# Connector.net
KiCad netlist of a schematic drawn in Altium Designer
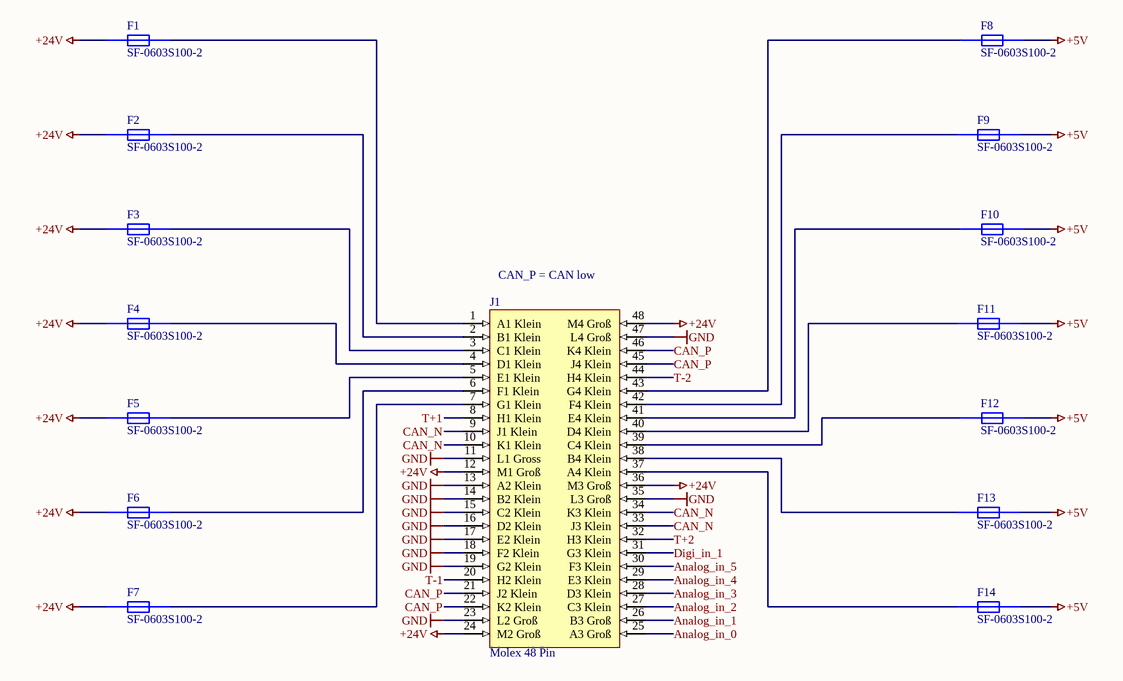
[diagram p0: Connector.SchDoc]

(export (version "E")
  (design (tool "Eeschema 10.0.6"))
  (components
    (comp (ref "F1")
      (value "SF-0603S100-2")
      (footprint "RESC1608X06N")
      (description "0603 SMD Slow Blow Fuse")
      (libsource (lib "LibMoritz") (part "SF-0603S100-2"))
    )
    (comp (ref "F2")
      (value "SF-0603S100-2")
      (footprint "RESC1608X06N")
      (description "0603 SMD Slow Blow Fuse")
      (libsource (lib "LibMoritz") (part "SF-0603S100-2"))
    )
    (comp (ref "F3")
      (value "SF-0603S100-2")
      (footprint "RESC1608X06N")
      (description "0603 SMD Slow Blow Fuse")
      (libsource (lib "LibMoritz") (part "SF-0603S100-2"))
    )
    (comp (ref "F4")
      (value "SF-0603S100-2")
      (footprint "RESC1608X06N")
      (description "0603 SMD Slow Blow Fuse")
      (libsource (lib "LibMoritz") (part "SF-0603S100-2"))
    )
    (comp (ref "F5")
      (value "SF-0603S100-2")
      (footprint "RESC1608X06N")
      (description "0603 SMD Slow Blow Fuse")
      (libsource (lib "LibMoritz") (part "SF-0603S100-2"))
    )
    (comp (ref "F6")
      (value "SF-0603S100-2")
      (footprint "RESC1608X06N")
      (description "0603 SMD Slow Blow Fuse")
      (libsource (lib "LibMoritz") (part "SF-0603S100-2"))
    )
    (comp (ref "F7")
      (value "SF-0603S100-2")
      (footprint "RESC1608X06N")
      (description "0603 SMD Slow Blow Fuse")
      (libsource (lib "LibMoritz") (part "SF-0603S100-2"))
    )
    (comp (ref "F8")
      (value "SF-0603S100-2")
      (footprint "RESC1608X06N")
      (description "0603 SMD Slow Blow Fuse")
      (libsource (lib "LibMoritz") (part "SF-0603S100-2"))
    )
    (comp (ref "F9")
      (value "SF-0603S100-2")
      (footprint "RESC1608X06N")
      (description "0603 SMD Slow Blow Fuse")
      (libsource (lib "LibMoritz") (part "SF-0603S100-2"))
    )
    (comp (ref "F10")
      (value "SF-0603S100-2")
      (footprint "RESC1608X06N")
      (description "0603 SMD Slow Blow Fuse")
      (libsource (lib "LibMoritz") (part "SF-0603S100-2"))
    )
    (comp (ref "F11")
      (value "SF-0603S100-2")
      (footprint "RESC1608X06N")
      (description "0603 SMD Slow Blow Fuse")
      (libsource (lib "LibMoritz") (part "SF-0603S100-2"))
    )
    (comp (ref "F12")
      (value "SF-0603S100-2")
      (footprint "RESC1608X06N")
      (description "0603 SMD Slow Blow Fuse")
      (libsource (lib "LibMoritz") (part "SF-0603S100-2"))
    )
    (comp (ref "F13")
      (value "SF-0603S100-2")
      (footprint "RESC1608X06N")
      (description "0603 SMD Slow Blow Fuse")
      (libsource (lib "LibMoritz") (part "SF-0603S100-2"))
    )
    (comp (ref "F14")
      (value "SF-0603S100-2")
      (footprint "RESC1608X06N")
      (description "0603 SMD Slow Blow Fuse")
      (libsource (lib "LibMoritz") (part "SF-0603S100-2"))
    )
    (comp (ref "J1")
      (value "Molex 48 Pin")
      (footprint "5007621001")
      (description "Molex 48 Pin CMC Header")
      (libsource (lib "LibMoritz") (part "5007621001"))
    )
  )
  (nets
    (net (code "1") (name "+5V") (class "Default")
      (node (ref "F10") (pin "2") (pinfunction "A2_2") (pintype "passive"))
      (node (ref "F11") (pin "2") (pinfunction "A2_2") (pintype "passive"))
      (node (ref "F12") (pin "2") (pinfunction "A2_2") (pintype "passive"))
      (node (ref "F13") (pin "2") (pinfunction "A2_2") (pintype "passive"))
      (node (ref "F14") (pin "2") (pinfunction "A2_2") (pintype "passive"))
      (node (ref "F8") (pin "2") (pinfunction "A2_2") (pintype "passive"))
      (node (ref "F9") (pin "2") (pinfunction "A2_2") (pintype "passive"))
    )
    (net (code "2") (name "+24V") (class "Default")
      (node (ref "F1") (pin "1") (pinfunction "A1_1") (pintype "passive"))
      (node (ref "F2") (pin "1") (pinfunction "A1_1") (pintype "passive"))
      (node (ref "F3") (pin "1") (pinfunction "A1_1") (pintype "passive"))
      (node (ref "F4") (pin "1") (pinfunction "A1_1") (pintype "passive"))
      (node (ref "F5") (pin "1") (pinfunction "A1_1") (pintype "passive"))
      (node (ref "F6") (pin "1") (pinfunction "A1_1") (pintype "passive"))
      (node (ref "F7") (pin "1") (pinfunction "A1_1") (pintype "passive"))
      (node (ref "J1") (pin "12") (pinfunction "M1_Groß_12") (pintype "input"))
      (node (ref "J1") (pin "24") (pinfunction "M2_Groß_24") (pintype "input"))
      (node (ref "J1") (pin "36") (pinfunction "M3_Groß_36") (pintype "input"))
      (node (ref "J1") (pin "48") (pinfunction "M4_Groß_48") (pintype "input"))
    )
    (net (code "3") (name "/Analog_in_0") (class "Default")
      (node (ref "J1") (pin "25") (pinfunction "A3_Groß_25") (pintype "input"))
    )
    (net (code "4") (name "/Analog_in_1") (class "Default")
      (node (ref "J1") (pin "26") (pinfunction "B3_Groß_26") (pintype "input"))
    )
    (net (code "5") (name "/Analog_in_2") (class "Default")
      (node (ref "J1") (pin "27") (pinfunction "C3_Klein_27") (pintype "input"))
    )
    (net (code "6") (name "/Analog_in_3") (class "Default")
      (node (ref "J1") (pin "28") (pinfunction "D3_Klein_28") (pintype "input"))
    )
    (net (code "7") (name "/Analog_in_4") (class "Default")
      (node (ref "J1") (pin "29") (pinfunction "E3_Klein_29") (pintype "input"))
    )
    (net (code "8") (name "/Analog_in_5") (class "Default")
      (node (ref "J1") (pin "30") (pinfunction "F3_Klein_30") (pintype "input"))
    )
    (net (code "9") (name "/CAN_N") (class "Default")
      (node (ref "J1") (pin "10") (pinfunction "K1_Klein_10") (pintype "input"))
      (node (ref "J1") (pin "33") (pinfunction "J3_Klein_33") (pintype "input"))
      (node (ref "J1") (pin "34") (pinfunction "K3_Klein_34") (pintype "input"))
      (node (ref "J1") (pin "9") (pinfunction "J1_Klein_9") (pintype "input"))
    )
    (net (code "10") (name "/CAN_P") (class "Default")
      (node (ref "J1") (pin "21") (pinfunction "J2_Klein_21") (pintype "input"))
      (node (ref "J1") (pin "22") (pinfunction "K2_Klein_22") (pintype "input"))
      (node (ref "J1") (pin "45") (pinfunction "J4_Klein_45") (pintype "input"))
      (node (ref "J1") (pin "46") (pinfunction "K4_Klein_46") (pintype "input"))
    )
    (net (code "11") (name "/Digi_in_1") (class "Default")
      (node (ref "J1") (pin "31") (pinfunction "G3_Klein_31") (pintype "input"))
    )
    (net (code "12") (name "/T+1") (class "Default")
      (node (ref "J1") (pin "8") (pinfunction "H1_Klein_8") (pintype "input"))
    )
    (net (code "13") (name "/T+2") (class "Default")
      (node (ref "J1") (pin "32") (pinfunction "H3_Klein_32") (pintype "input"))
    )
    (net (code "14") (name "/T-1") (class "Default")
      (node (ref "J1") (pin "20") (pinfunction "H2_Klein_20") (pintype "input"))
    )
    (net (code "15") (name "/T-2") (class "Default")
      (node (ref "J1") (pin "44") (pinfunction "H4_Klein_44") (pintype "input"))
    )
    (net (code "16") (name "GND") (class "Default")
      (node (ref "J1") (pin "11") (pinfunction "L1_Gross_11") (pintype "input"))
      (node (ref "J1") (pin "13") (pinfunction "A2_Klein_13") (pintype "input"))
      (node (ref "J1") (pin "14") (pinfunction "B2_Klein_14") (pintype "input"))
      (node (ref "J1") (pin "15") (pinfunction "C2_Klein_15") (pintype "input"))
      (node (ref "J1") (pin "16") (pinfunction "D2_Klein_16") (pintype "input"))
      (node (ref "J1") (pin "17") (pinfunction "E2_Klein_17") (pintype "input"))
      (node (ref "J1") (pin "18") (pinfunction "F2_Klein_18") (pintype "input"))
      (node (ref "J1") (pin "19") (pinfunction "G2_Klein_19") (pintype "input"))
      (node (ref "J1") (pin "23") (pinfunction "L2_Groß_23") (pintype "input"))
      (node (ref "J1") (pin "35") (pinfunction "L3_Groß_35") (pintype "input"))
      (node (ref "J1") (pin "47") (pinfunction "L4_Groß_47") (pintype "input"))
    )
    (net (code "17") (name "Net-(F1-A2)") (class "Default")
      (node (ref "F1") (pin "2") (pinfunction "A2_2") (pintype "passive"))
      (node (ref "J1") (pin "1") (pinfunction "A1_Klein_1") (pintype "input"))
    )
    (net (code "18") (name "Net-(F2-A2)") (class "Default")
      (node (ref "F2") (pin "2") (pinfunction "A2_2") (pintype "passive"))
      (node (ref "J1") (pin "2") (pinfunction "B1_Klein_2") (pintype "input"))
    )
    (net (code "19") (name "Net-(F3-A2)") (class "Default")
      (node (ref "F3") (pin "2") (pinfunction "A2_2") (pintype "passive"))
      (node (ref "J1") (pin "3") (pinfunction "C1_Klein_3") (pintype "input"))
    )
    (net (code "20") (name "Net-(F4-A2)") (class "Default")
      (node (ref "F4") (pin "2") (pinfunction "A2_2") (pintype "passive"))
      (node (ref "J1") (pin "4") (pinfunction "D1_Klein_4") (pintype "input"))
    )
    (net (code "21") (name "Net-(F5-A2)") (class "Default")
      (node (ref "F5") (pin "2") (pinfunction "A2_2") (pintype "passive"))
      (node (ref "J1") (pin "5") (pinfunction "E1_Klein_5") (pintype "input"))
    )
    (net (code "22") (name "Net-(F6-A2)") (class "Default")
      (node (ref "F6") (pin "2") (pinfunction "A2_2") (pintype "passive"))
      (node (ref "J1") (pin "6") (pinfunction "F1_Klein_6") (pintype "input"))
    )
    (net (code "23") (name "Net-(F7-A2)") (class "Default")
      (node (ref "F7") (pin "2") (pinfunction "A2_2") (pintype "passive"))
      (node (ref "J1") (pin "7") (pinfunction "G1_Klein_7") (pintype "input"))
    )
    (net (code "24") (name "Net-(F8-A1)") (class "Default")
      (node (ref "F8") (pin "1") (pinfunction "A1_1") (pintype "passive"))
      (node (ref "J1") (pin "43") (pinfunction "G4_Klein_43") (pintype "input"))
    )
    (net (code "25") (name "Net-(F9-A1)") (class "Default")
      (node (ref "F9") (pin "1") (pinfunction "A1_1") (pintype "passive"))
      (node (ref "J1") (pin "42") (pinfunction "F4_Klein_42") (pintype "input"))
    )
    (net (code "26") (name "Net-(F10-A1)") (class "Default")
      (node (ref "F10") (pin "1") (pinfunction "A1_1") (pintype "passive"))
      (node (ref "J1") (pin "41") (pinfunction "E4_Klein_41") (pintype "input"))
    )
    (net (code "27") (name "Net-(F11-A1)") (class "Default")
      (node (ref "F11") (pin "1") (pinfunction "A1_1") (pintype "passive"))
      (node (ref "J1") (pin "40") (pinfunction "D4_Klein_40") (pintype "input"))
    )
    (net (code "28") (name "Net-(F12-A1)") (class "Default")
      (node (ref "F12") (pin "1") (pinfunction "A1_1") (pintype "passive"))
      (node (ref "J1") (pin "39") (pinfunction "C4_Klein_39") (pintype "input"))
    )
    (net (code "29") (name "Net-(F13-A1)") (class "Default")
      (node (ref "F13") (pin "1") (pinfunction "A1_1") (pintype "passive"))
      (node (ref "J1") (pin "38") (pinfunction "B4_Klein_38") (pintype "input"))
    )
    (net (code "30") (name "Net-(F14-A1)") (class "Default")
      (node (ref "F14") (pin "1") (pinfunction "A1_1") (pintype "passive"))
      (node (ref "J1") (pin "37") (pinfunction "A4_Klein_37") (pintype "input"))
    )
  )
)
